# PCM1822Q1.net
KiCad netlist of a schematic drawn in Altium Designer
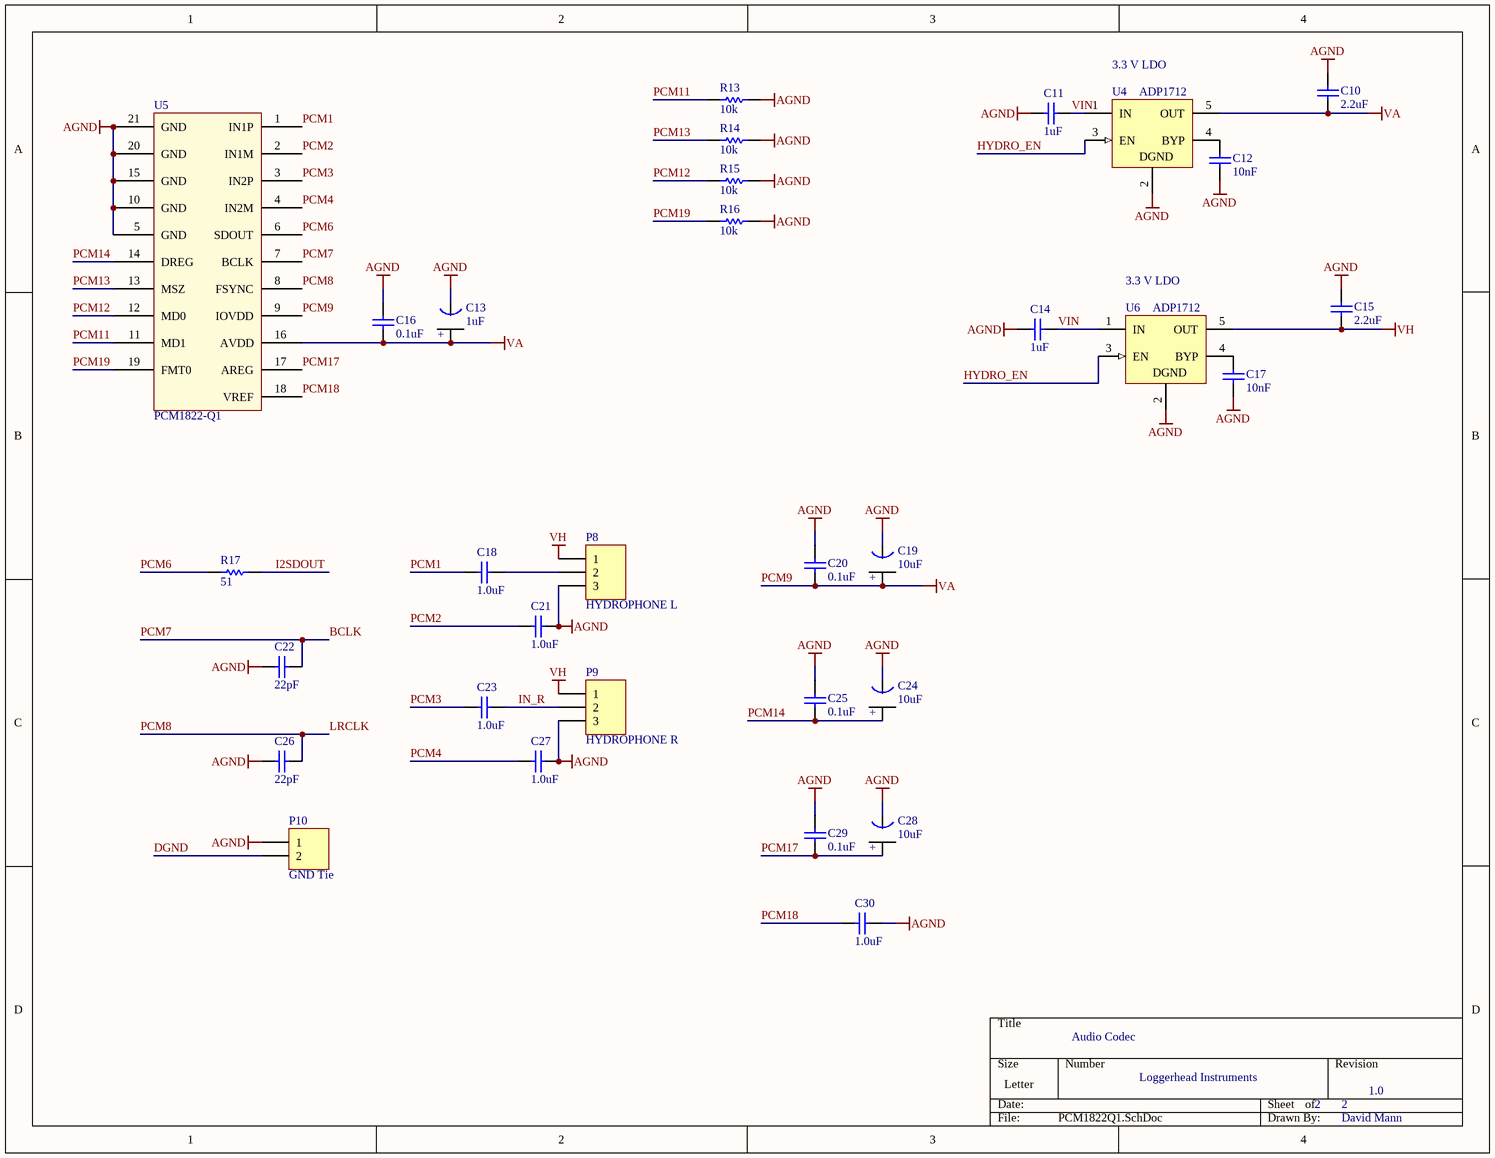
[diagram p0: PCM1822Q1.SchDoc]

(export (version "E")
  (design (tool "Eeschema 10.0.6"))
  (components
    (comp (ref "C10")
      (value "2.2uF")
      (footprint "0402")
      (description "Ceramic Chip Capacitor - Standard")
      (fields (field (name "PUBLISHER") "Altium Limited"))
      (libsource (lib "KEMET Chip Capacitor") (part "C0402"))
    )
    (comp (ref "C11")
      (value "1uF")
      (footprint "0402")
      (description "Ceramic Chip Capacitor - Standard")
      (fields (field (name "PUBLISHER") "Altium Limited"))
      (libsource (lib "KEMET Chip Capacitor") (part "C0402"))
    )
    (comp (ref "C12")
      (value "10nF")
      (footprint "0402")
      (description "Ceramic Chip Capacitor - Standard")
      (fields (field (name "PUBLISHER") "Altium Limited"))
      (libsource (lib "KEMET Chip Capacitor") (part "C0402"))
    )
    (comp (ref "C13") (value "1uF") (footprint "Tant0805") (libsource (lib "Loggerhead") (part "Tant0805")))
    (comp (ref "C14")
      (value "1uF")
      (footprint "0402")
      (description "Ceramic Chip Capacitor - Standard")
      (fields (field (name "PUBLISHER") "Altium Limited"))
      (libsource (lib "KEMET Chip Capacitor") (part "C0402"))
    )
    (comp (ref "C15")
      (value "2.2uF")
      (footprint "0402")
      (description "Ceramic Chip Capacitor - Standard")
      (fields (field (name "PUBLISHER") "Altium Limited"))
      (libsource (lib "KEMET Chip Capacitor") (part "C0402"))
    )
    (comp (ref "C16")
      (value "0.1uF")
      (footprint "0402")
      (description "Ceramic Chip Capacitor - Standard")
      (fields (field (name "PUBLISHER") "Altium Limited"))
      (libsource (lib "KEMET Chip Capacitor") (part "C0402"))
    )
    (comp (ref "C17")
      (value "10nF")
      (footprint "0402")
      (description "Ceramic Chip Capacitor - Standard")
      (fields (field (name "PUBLISHER") "Altium Limited"))
      (libsource (lib "KEMET Chip Capacitor") (part "C0402"))
    )
    (comp (ref "C18")
      (value "1.0uF")
      (footprint "0402")
      (description "Ceramic Chip Capacitor - Standard")
      (fields (field (name "PUBLISHER") "Altium Limited"))
      (libsource (lib "KEMET Chip Capacitor") (part "C0402"))
    )
    (comp (ref "C19") (value "10uF") (footprint "Tant0805") (libsource (lib "Loggerhead") (part "Tant0805")))
    (comp (ref "C20")
      (value "0.1uF")
      (footprint "0402")
      (description "Ceramic Chip Capacitor - Standard")
      (fields (field (name "PUBLISHER") "Altium Limited"))
      (libsource (lib "KEMET Chip Capacitor") (part "C0402"))
    )
    (comp (ref "C21")
      (value "1.0uF")
      (footprint "0402")
      (description "Ceramic Chip Capacitor - Standard")
      (fields (field (name "PUBLISHER") "Altium Limited"))
      (libsource (lib "KEMET Chip Capacitor") (part "C0402"))
    )
    (comp (ref "C22")
      (value "22pF")
      (footprint "0402")
      (description "Ceramic Chip Capacitor - Standard")
      (fields (field (name "PUBLISHER") "Altium Limited"))
      (libsource (lib "KEMET Chip Capacitor") (part "C0402"))
    )
    (comp (ref "C23")
      (value "1.0uF")
      (footprint "0402")
      (description "Ceramic Chip Capacitor - Standard")
      (fields (field (name "PUBLISHER") "Altium Limited"))
      (libsource (lib "KEMET Chip Capacitor") (part "C0402"))
    )
    (comp (ref "C24") (value "10uF") (footprint "Tant0805") (libsource (lib "Loggerhead") (part "Tant0805")))
    (comp (ref "C25")
      (value "0.1uF")
      (footprint "0402")
      (description "Ceramic Chip Capacitor - Standard")
      (fields (field (name "PUBLISHER") "Altium Limited"))
      (libsource (lib "KEMET Chip Capacitor") (part "C0402"))
    )
    (comp (ref "C26")
      (value "22pF")
      (footprint "0402")
      (description "Ceramic Chip Capacitor - Standard")
      (fields (field (name "PUBLISHER") "Altium Limited"))
      (libsource (lib "KEMET Chip Capacitor") (part "C0402"))
    )
    (comp (ref "C27")
      (value "1.0uF")
      (footprint "0402")
      (description "Ceramic Chip Capacitor - Standard")
      (fields (field (name "PUBLISHER") "Altium Limited"))
      (libsource (lib "KEMET Chip Capacitor") (part "C0402"))
    )
    (comp (ref "C28") (value "10uF") (footprint "Tant0805") (libsource (lib "Loggerhead") (part "Tant0805")))
    (comp (ref "C29")
      (value "0.1uF")
      (footprint "0402")
      (description "Ceramic Chip Capacitor - Standard")
      (fields (field (name "PUBLISHER") "Altium Limited"))
      (libsource (lib "KEMET Chip Capacitor") (part "C0402"))
    )
    (comp (ref "C30")
      (value "1.0uF")
      (footprint "0402")
      (description "Ceramic Chip Capacitor - Standard")
      (fields (field (name "PUBLISHER") "Altium Limited"))
      (libsource (lib "KEMET Chip Capacitor") (part "C0402"))
    )
    (comp (ref "P8")
      (value "HYDROPHONE L")
      (footprint "HDR1X3")
      (description "Header, 3-Pin")
      (fields (field (name "PUBLISHER") "Altium Limited"))
      (libsource (lib "Miscellaneous Connectors") (part "Header 3"))
    )
    (comp (ref "P9")
      (value "HYDROPHONE R")
      (footprint "HDR1X3")
      (description "Header, 3-Pin")
      (fields (field (name "PUBLISHER") "Altium Limited"))
      (libsource (lib "Miscellaneous Connectors") (part "Header 3"))
    )
    (comp (ref "P10")
      (value "GND Tie")
      (footprint "HDR1X2")
      (description "Header, 2-Pin")
      (fields (field (name "PUBLISHER") "Altium Limited"))
      (libsource (lib "Miscellaneous Connectors") (part "Header 2"))
    )
    (comp (ref "R13")
      (value "10k")
      (footprint "3-0603")
      (fields (field (name "PUBLISHER") "Altium Limited"))
      (libsource (lib "Panasonic Resistor") (part "ERJ3RK"))
    )
    (comp (ref "R14")
      (value "10k")
      (footprint "3-0603")
      (fields (field (name "PUBLISHER") "Altium Limited"))
      (libsource (lib "Panasonic Resistor") (part "ERJ3RK"))
    )
    (comp (ref "R15")
      (value "10k")
      (footprint "3-0603")
      (fields (field (name "PUBLISHER") "Altium Limited"))
      (libsource (lib "Panasonic Resistor") (part "ERJ3RK"))
    )
    (comp (ref "R16")
      (value "10k")
      (footprint "3-0603")
      (fields (field (name "PUBLISHER") "Altium Limited"))
      (libsource (lib "Panasonic Resistor") (part "ERJ3RK"))
    )
    (comp (ref "R17")
      (value "51")
      (footprint "3-0603")
      (fields (field (name "PUBLISHER") "Altium Limited"))
      (libsource (lib "Panasonic Resistor") (part "ERJ3RK"))
    )
    (comp (ref "U4")
      (value "ADP1712")
      (footprint "MF05A_N")
      (description "Micropower, 150mA Low-Noise Ultra Low-Dropout CMOS Voltage Regulator")
      (fields
        (field (name "PARTNUMBER") "LP3985IM5-3.3")
        (field (name "MANUFACTURER") "National Semiconductor")
        (field (name "PUBLISHER") "Altium Limited")
      )
      (libsource (lib "NSC LDO") (part "LP3985IM5-3.3"))
    )
    (comp (ref "U5")
      (value "PCM1822-Q1")
      (footprint "PCM1822-Q1")
      (description "TI PCM1822-Q1 Stereo Channel, 32-Bit, 192-kHz, Burr-Brown Audio ADC")
      (libsource (lib "Loggerhead") (part "PCM1822-Q1"))
    )
    (comp (ref "U6")
      (value "ADP1712")
      (footprint "MF05A_N")
      (description "Micropower, 150mA Low-Noise Ultra Low-Dropout CMOS Voltage Regulator")
      (fields
        (field (name "PARTNUMBER") "LP3985IM5-3.3")
        (field (name "MANUFACTURER") "National Semiconductor")
        (field (name "PUBLISHER") "Altium Limited")
      )
      (libsource (lib "NSC LDO") (part "LP3985IM5-3.3"))
    )
  )
  (nets
    (net (code "1") (name "/BCLK") (class "Default")
      (node (ref "C22") (pin "2") (pinfunction "2_2") (pintype "passive"))
      (node (ref "U5") (pin "7") (pinfunction "BCLK_7") (pintype "passive"))
    )
    (net (code "2") (name "/DGND") (class "Default")
      (node (ref "P10") (pin "2") (pinfunction "2_2") (pintype "passive"))
    )
    (net (code "3") (name "/HYDRO_EN") (class "Default")
      (node (ref "U4") (pin "3") (pinfunction "EN_3") (pintype "input"))
      (node (ref "U6") (pin "3") (pinfunction "EN_3") (pintype "input"))
    )
    (net (code "4") (name "/I2SDOUT") (class "Default")
      (node (ref "R17") (pin "2") (pinfunction "2_2") (pintype "passive"))
    )
    (net (code "5") (name "/IN_R") (class "Default")
      (node (ref "C23") (pin "1") (pinfunction "1_1") (pintype "passive"))
      (node (ref "P9") (pin "2") (pinfunction "2_2") (pintype "passive"))
    )
    (net (code "6") (name "/LRCLK") (class "Default")
      (node (ref "C26") (pin "2") (pinfunction "2_2") (pintype "passive"))
      (node (ref "U5") (pin "8") (pinfunction "FSYNC_8") (pintype "passive"))
    )
    (net (code "7") (name "/PCM1") (class "Default")
      (node (ref "C18") (pin "2") (pinfunction "2_2") (pintype "passive"))
      (node (ref "U5") (pin "1") (pinfunction "IN1P_1") (pintype "passive"))
    )
    (net (code "8") (name "/PCM2") (class "Default")
      (node (ref "C21") (pin "2") (pinfunction "2_2") (pintype "passive"))
      (node (ref "U5") (pin "2") (pinfunction "IN1M_2") (pintype "passive"))
    )
    (net (code "9") (name "/PCM3") (class "Default")
      (node (ref "C23") (pin "2") (pinfunction "2_2") (pintype "passive"))
      (node (ref "U5") (pin "3") (pinfunction "IN2P_3") (pintype "passive"))
    )
    (net (code "10") (name "/PCM4") (class "Default")
      (node (ref "C27") (pin "2") (pinfunction "2_2") (pintype "passive"))
      (node (ref "U5") (pin "4") (pinfunction "IN2M_4") (pintype "passive"))
    )
    (net (code "11") (name "/PCM6") (class "Default")
      (node (ref "R17") (pin "1") (pinfunction "1_1") (pintype "passive"))
      (node (ref "U5") (pin "6") (pinfunction "SDOUT_6") (pintype "passive"))
    )
    (net (code "12") (name "/PCM11") (class "Default")
      (node (ref "R13") (pin "1") (pinfunction "1_1") (pintype "passive"))
      (node (ref "U5") (pin "11") (pinfunction "MD1_11") (pintype "passive"))
    )
    (net (code "13") (name "/PCM12") (class "Default")
      (node (ref "R15") (pin "1") (pinfunction "1_1") (pintype "passive"))
      (node (ref "U5") (pin "12") (pinfunction "MD0_12") (pintype "passive"))
    )
    (net (code "14") (name "/PCM13") (class "Default")
      (node (ref "R14") (pin "1") (pinfunction "1_1") (pintype "passive"))
      (node (ref "U5") (pin "13") (pinfunction "MSZ_13") (pintype "passive"))
    )
    (net (code "15") (name "/PCM14") (class "Default")
      (node (ref "C24") (pin "2") (pinfunction "+_2") (pintype "passive"))
      (node (ref "C25") (pin "2") (pinfunction "2_2") (pintype "passive"))
      (node (ref "U5") (pin "14") (pinfunction "DREG_14") (pintype "passive"))
    )
    (net (code "16") (name "/PCM17") (class "Default")
      (node (ref "C28") (pin "2") (pinfunction "+_2") (pintype "passive"))
      (node (ref "C29") (pin "2") (pinfunction "2_2") (pintype "passive"))
      (node (ref "U5") (pin "17") (pinfunction "AREG_17") (pintype "passive"))
    )
    (net (code "17") (name "/PCM18") (class "Default")
      (node (ref "C30") (pin "2") (pinfunction "2_2") (pintype "passive"))
      (node (ref "U5") (pin "18") (pinfunction "VREF_18") (pintype "passive"))
    )
    (net (code "18") (name "/PCM19") (class "Default")
      (node (ref "R16") (pin "1") (pinfunction "1_1") (pintype "passive"))
      (node (ref "U5") (pin "19") (pinfunction "FMT0_19") (pintype "passive"))
    )
    (net (code "19") (name "/VIN") (class "Default")
      (node (ref "C11") (pin "1") (pinfunction "1_1") (pintype "passive"))
      (node (ref "C14") (pin "1") (pinfunction "1_1") (pintype "passive"))
      (node (ref "U4") (pin "1") (pinfunction "IN_1") (pintype "power_in"))
      (node (ref "U6") (pin "1") (pinfunction "IN_1") (pintype "power_in"))
    )
    (net (code "20") (name "AGND") (class "Default")
      (node (ref "C10") (pin "2") (pinfunction "2_2") (pintype "passive"))
      (node (ref "C11") (pin "2") (pinfunction "2_2") (pintype "passive"))
      (node (ref "C12") (pin "2") (pinfunction "2_2") (pintype "passive"))
      (node (ref "C13") (pin "1") (pinfunction "GND_1") (pintype "passive"))
      (node (ref "C14") (pin "2") (pinfunction "2_2") (pintype "passive"))
      (node (ref "C15") (pin "2") (pinfunction "2_2") (pintype "passive"))
      (node (ref "C16") (pin "1") (pinfunction "1_1") (pintype "passive"))
      (node (ref "C17") (pin "2") (pinfunction "2_2") (pintype "passive"))
      (node (ref "C19") (pin "1") (pinfunction "GND_1") (pintype "passive"))
      (node (ref "C20") (pin "1") (pinfunction "1_1") (pintype "passive"))
      (node (ref "C21") (pin "1") (pinfunction "1_1") (pintype "passive"))
      (node (ref "C22") (pin "1") (pinfunction "1_1") (pintype "passive"))
      (node (ref "C24") (pin "1") (pinfunction "GND_1") (pintype "passive"))
      (node (ref "C25") (pin "1") (pinfunction "1_1") (pintype "passive"))
      (node (ref "C26") (pin "1") (pinfunction "1_1") (pintype "passive"))
      (node (ref "C27") (pin "1") (pinfunction "1_1") (pintype "passive"))
      (node (ref "C28") (pin "1") (pinfunction "GND_1") (pintype "passive"))
      (node (ref "C29") (pin "1") (pinfunction "1_1") (pintype "passive"))
      (node (ref "C30") (pin "1") (pinfunction "1_1") (pintype "passive"))
      (node (ref "P10") (pin "1") (pinfunction "1_1") (pintype "passive"))
      (node (ref "P8") (pin "3") (pinfunction "3_3") (pintype "passive"))
      (node (ref "P9") (pin "3") (pinfunction "3_3") (pintype "passive"))
      (node (ref "R13") (pin "2") (pinfunction "2_2") (pintype "passive"))
      (node (ref "R14") (pin "2") (pinfunction "2_2") (pintype "passive"))
      (node (ref "R15") (pin "2") (pinfunction "2_2") (pintype "passive"))
      (node (ref "R16") (pin "2") (pinfunction "2_2") (pintype "passive"))
      (node (ref "U4") (pin "2") (pinfunction "GND_2") (pintype "power_in"))
      (node (ref "U5") (pin "10") (pinfunction "GND_10") (pintype "passive"))
      (node (ref "U5") (pin "15") (pinfunction "GND_15") (pintype "passive"))
      (node (ref "U5") (pin "20") (pinfunction "GND_20") (pintype "passive"))
      (node (ref "U5") (pin "21") (pinfunction "GND_21") (pintype "passive"))
      (node (ref "U5") (pin "5") (pinfunction "GND_5") (pintype "passive"))
      (node (ref "U6") (pin "2") (pinfunction "GND_2") (pintype "power_in"))
    )
    (net (code "21") (name "Net-(C18-Pad1)") (class "Default")
      (node (ref "C18") (pin "1") (pinfunction "1_1") (pintype "passive"))
      (node (ref "P8") (pin "2") (pinfunction "2_2") (pintype "passive"))
    )
    (net (code "22") (name "Net-(U4-BYP)") (class "Default")
      (node (ref "C12") (pin "1") (pinfunction "1_1") (pintype "passive"))
      (node (ref "U4") (pin "4") (pinfunction "BYP_4") (pintype "passive"))
    )
    (net (code "23") (name "Net-(U6-BYP)") (class "Default")
      (node (ref "C17") (pin "1") (pinfunction "1_1") (pintype "passive"))
      (node (ref "U6") (pin "4") (pinfunction "BYP_4") (pintype "passive"))
    )
    (net (code "24") (name "VA") (class "Default")
      (node (ref "C10") (pin "1") (pinfunction "1_1") (pintype "passive"))
      (node (ref "C13") (pin "2") (pinfunction "+_2") (pintype "passive"))
      (node (ref "C16") (pin "2") (pinfunction "2_2") (pintype "passive"))
      (node (ref "C19") (pin "2") (pinfunction "+_2") (pintype "passive"))
      (node (ref "C20") (pin "2") (pinfunction "2_2") (pintype "passive"))
      (node (ref "U4") (pin "5") (pinfunction "OUT_5") (pintype "power_in"))
      (node (ref "U5") (pin "16") (pinfunction "AVDD_16") (pintype "passive"))
      (node (ref "U5") (pin "9") (pinfunction "IOVDD_9") (pintype "passive"))
    )
    (net (code "25") (name "VH") (class "Default")
      (node (ref "C15") (pin "1") (pinfunction "1_1") (pintype "passive"))
      (node (ref "P8") (pin "1") (pinfunction "1_1") (pintype "passive"))
      (node (ref "P9") (pin "1") (pinfunction "1_1") (pintype "passive"))
      (node (ref "U6") (pin "5") (pinfunction "OUT_5") (pintype "power_in"))
    )
  )
)
